# Light_Control.net
KiCad netlist of a schematic drawn in Altium Designer
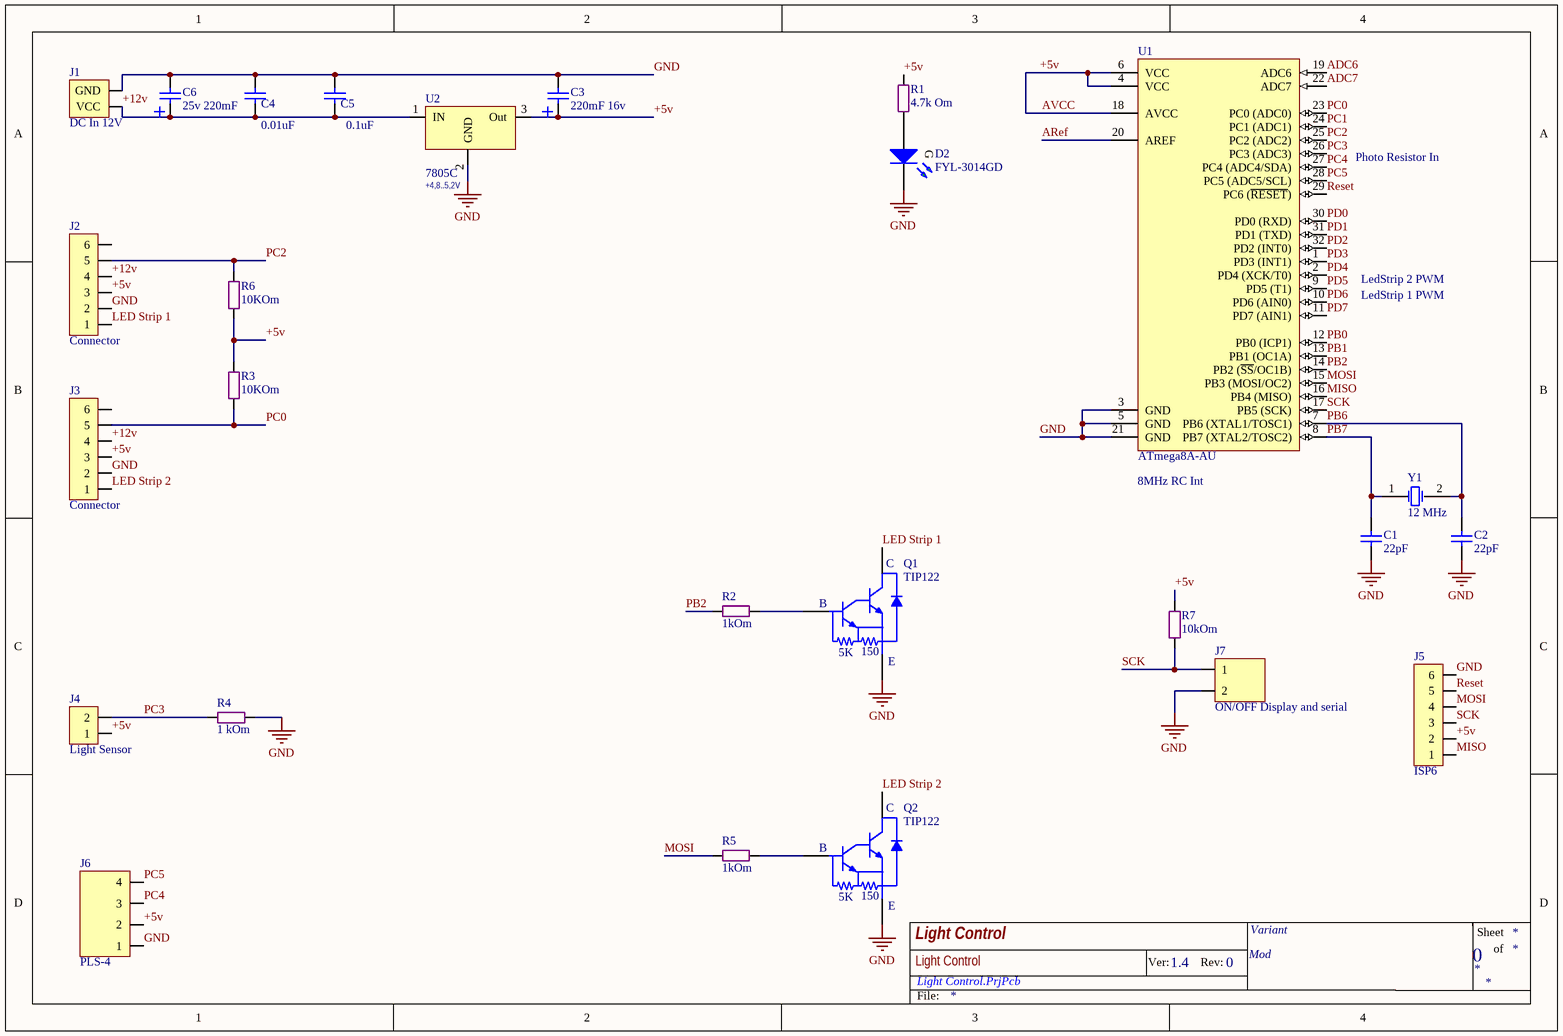
[diagram p0: Light Control.SchDoc]

(export (version "E")
  (design (tool "Eeschema 10.0.6"))
  (components
    (comp (ref "C1")
      (value "22pF")
      (footprint "Capacitor:SMD 0805 (2012)")
      (description "Capacitor")
      (libsource (lib "Capacitor") (part "Cap SMD 0402-1812"))
    )
    (comp (ref "C2")
      (value "22pF")
      (footprint "Capacitor:SMD 0805 (2012)")
      (description "Capacitor")
      (libsource (lib "Capacitor") (part "Cap SMD 0402-1812"))
    )
    (comp (ref "C3")
      (value "220mF 16v")
      (footprint "Capacitor:Cap E p2mm D6.5xH11")
      (description "Capacitor")
      (libsource (lib "Capacitor") (part "Cap E 220mF x 16V"))
    )
    (comp (ref "C4")
      (value "0.01uF")
      (footprint "Capacitor:SMD 0805 (2012)")
      (description "Capacitor")
      (libsource (lib "Capacitor") (part "Cap SMD 0402-1812"))
    )
    (comp (ref "C5")
      (value "0.1uF")
      (footprint "Capacitor:SMD 0805 (2012)")
      (description "Capacitor")
      (libsource (lib "Capacitor") (part "Cap SMD 0402-1812"))
    )
    (comp (ref "C6")
      (value "25v 220mF")
      (footprint "Capacitor:Cap E p2mm D6.5xH11")
      (description "Capacitor")
      (libsource (lib "Capacitor") (part "Cap E 220mF x 16V"))
    )
    (comp (ref "D2")
      (value "FYL-3014GD")
      (footprint "LED:LED Round 3mm Green")
      (description "2.1v 10mA, 15-30mCd")
      (libsource (lib "LED") (part "Led Round 3mm Green"))
    )
    (comp (ref "J1")
      (value "DC In 12V")
      (footprint "Connector:DC Connector")
      (description "DC Connector")
      (libsource (lib "Connector") (part "DC Connector (PJ-002B)"))
    )
    (comp (ref "J2")
      (value "Connector")
      (footprint "Connector:Molex Micro-Fit 3.0 - 6 pin D R")
      (description "Horisontal, Dbl line, Male - 3mm")
      (libsource (lib "Connector") (part "Micro-Fit 6R (2x3)"))
    )
    (comp (ref "J3")
      (value "Connector")
      (footprint "Connector:Molex Micro-Fit 3.0 - 6 pin D R")
      (description "Horisontal, Dbl line, Male - 3mm")
      (libsource (lib "Connector") (part "Micro-Fit 6R (2x3)"))
    )
    (comp (ref "J4")
      (value "Light Sensor")
      (footprint "Connector:Molex Micro-Fit 3.0 - 2 pin D R")
      (description "Horisontal, Dbl line, Male - 3mm")
      (fields (field (name "PART NUMBER") "430450200"))
      (libsource (lib "Connector") (part "Micro-Fit 2R (1x2)"))
    )
    (comp (ref "J5")
      (value "ISP6")
      (footprint "Connector:LINE 2.54 x 6D (2 x 3)")
      (description "Vert, Dbl line, Male")
      (libsource (lib "Connector") (part "PLD-6 (2 x 3)"))
    )
    (comp (ref "J6")
      (value "PLS-4")
      (footprint "Connector:Line 2.54 X 4")
      (description "Vert, Sgl line, Male")
      (libsource (lib "Connector") (part "PLS-4"))
    )
    (comp (ref "J7")
      (value "ON/OFF Display and serial")
      (footprint "Connector:Line 2.54 x 2")
      (description "Vert, Sgl line, Male")
      (libsource (lib "Connector") (part "PLS-2"))
    )
    (comp (ref "Q1")
      (value "TIP122")
      (footprint "GeneralCases:TO220-2")
      (description "NPN Darlington 5A, 65W, 100V, h>1000")
      (libsource (lib "Transistor") (part "TIP122"))
    )
    (comp (ref "Q2")
      (value "TIP122")
      (footprint "GeneralCases:TO220-2")
      (description "NPN Darlington 5A, 65W, 100V, h>1000")
      (libsource (lib "Transistor") (part "TIP122"))
    )
    (comp (ref "R1")
      (value "4.7k Om")
      (footprint "PassiveComponents:SMD 0805 (2012)")
      (libsource (lib "PassiveComponents") (part "Res All Types"))
    )
    (comp (ref "R2")
      (value "1kOm")
      (footprint "PassiveComponents:Res 0.25w - 7p")
      (libsource (lib "PassiveComponents") (part "Res All Types"))
    )
    (comp (ref "R3")
      (value "10KOm")
      (footprint "PassiveComponents:SMD 0805 (2012)")
      (libsource (lib "PassiveComponents") (part "Res All Types"))
    )
    (comp (ref "R4")
      (value "1 kOm")
      (footprint "PassiveComponents:SMD 0805 (2012)")
      (libsource (lib "PassiveComponents") (part "Res All Types"))
    )
    (comp (ref "R5")
      (value "1kOm")
      (footprint "PassiveComponents:SMD 1206 (3216)")
      (libsource (lib "PassiveComponents") (part "Res All Types"))
    )
    (comp (ref "R6")
      (value "10KOm")
      (footprint "PassiveComponents:SMD 0805 (2012)")
      (libsource (lib "PassiveComponents") (part "Res All Types"))
    )
    (comp (ref "R7")
      (value "10kOm")
      (footprint "PassiveComponents:SMD 0805 (2012)")
      (libsource (lib "PassiveComponents") (part "Res All Types"))
    )
    (comp (ref "U1")
      (value "ATmega8A-AU")
      (footprint "32A_M")
      (fields (field (name "PUBLISHER") "Altium Limited"))
      (libsource (lib "Atmel Microcontroller 8-Bit megaAVR") (part "ATmega8A-AU"))
    )
    (comp (ref "U2")
      (value "7805C")
      (footprint "GeneralCases:D-PAK")
      (description "Voltage Regulator")
      (fields (field (name "MANUFACTURER") "Интеграл") (field (name "V OUT") "+4,8..5,2V"))
      (libsource (lib "PowerAdjusment") (part "7805C"))
    )
    (comp (ref "Y1")
      (value "12 MHz")
      (footprint "PassiveComponents:XTAL - 2")
      (description "Crystal Oscillator")
      (fields (field (name "PUBLISHER") "Altium Limited"))
      (libsource (lib "PassiveComponents") (part "XTAL"))
    )
  )
  (nets
    (net (code "1") (name "/+5v") (class "Default")
      (node (ref "C3") (pin "1") (pinfunction "1_1") (pintype "passive"))
      (node (ref "J2") (pin "3") (pinfunction "3_3") (pintype "passive"))
      (node (ref "J3") (pin "3") (pinfunction "3_3") (pintype "passive"))
      (node (ref "J4") (pin "1") (pinfunction "1_1") (pintype "passive"))
      (node (ref "J5") (pin "2") (pinfunction "2_2") (pintype "passive"))
      (node (ref "J6") (pin "2") (pinfunction "2_2") (pintype "passive"))
      (node (ref "R1") (pin "1") (pinfunction "1_1") (pintype "passive"))
      (node (ref "R3") (pin "2") (pinfunction "2_2") (pintype "passive"))
      (node (ref "R6") (pin "1") (pinfunction "1_1") (pintype "passive"))
      (node (ref "R7") (pin "2") (pinfunction "2_2") (pintype "passive"))
      (node (ref "U1") (pin "18") (pinfunction "AVCC_18") (pintype "power_in"))
      (node (ref "U1") (pin "4") (pinfunction "VCC_4") (pintype "power_in"))
      (node (ref "U1") (pin "6") (pinfunction "VCC_6") (pintype "power_in"))
      (node (ref "U2") (pin "3") (pinfunction "Out_3") (pintype "power_in"))
    )
    (net (code "2") (name "/+12v") (class "Default")
      (node (ref "C4") (pin "2") (pinfunction "2_2") (pintype "passive"))
      (node (ref "C5") (pin "2") (pinfunction "2_2") (pintype "passive"))
      (node (ref "C6") (pin "1") (pinfunction "1_1") (pintype "passive"))
      (node (ref "J1") (pin "VCC") (pinfunction "VCC_VCC") (pintype "passive"))
      (node (ref "J2") (pin "4") (pinfunction "4_4") (pintype "passive"))
      (node (ref "J3") (pin "4") (pinfunction "4_4") (pintype "passive"))
      (node (ref "U2") (pin "1") (pinfunction "IN_1") (pintype "power_in"))
    )
    (net (code "3") (name "/ADC6") (class "Default")
      (node (ref "U1") (pin "19") (pinfunction "ADC6_19") (pintype "input"))
    )
    (net (code "4") (name "/ADC7") (class "Default")
      (node (ref "U1") (pin "22") (pinfunction "ADC7_22") (pintype "input"))
    )
    (net (code "5") (name "/ARef") (class "Default")
      (node (ref "U1") (pin "20") (pinfunction "AREF_20") (pintype "power_in"))
    )
    (net (code "6") (name "/LED Strip 1") (class "Default")
      (node (ref "J2") (pin "1") (pinfunction "1_1") (pintype "passive"))
      (node (ref "Q1") (pin "2") (pinfunction "C_2") (pintype "passive"))
    )
    (net (code "7") (name "/LED Strip 2") (class "Default")
      (node (ref "J3") (pin "1") (pinfunction "1_1") (pintype "passive"))
      (node (ref "Q2") (pin "2") (pinfunction "C_2") (pintype "passive"))
    )
    (net (code "8") (name "/MISO") (class "Default")
      (node (ref "J5") (pin "1") (pinfunction "1_1") (pintype "passive"))
      (node (ref "U1") (pin "16") (pinfunction "PB4_(MISO)_16") (pintype "bidirectional"))
    )
    (net (code "9") (name "/MOSI") (class "Default")
      (node (ref "J5") (pin "4") (pinfunction "4_4") (pintype "passive"))
      (node (ref "R5") (pin "1") (pinfunction "1_1") (pintype "passive"))
      (node (ref "U1") (pin "15") (pinfunction "PB3_(MOSI/OC2)_15") (pintype "bidirectional"))
    )
    (net (code "10") (name "/PB0") (class "Default")
      (node (ref "U1") (pin "12") (pinfunction "PB0_(ICP1)_12") (pintype "bidirectional"))
    )
    (net (code "11") (name "/PB1") (class "Default")
      (node (ref "U1") (pin "13") (pinfunction "PB1_(OC1A)_13") (pintype "bidirectional"))
    )
    (net (code "12") (name "/PB2") (class "Default")
      (node (ref "R2") (pin "1") (pinfunction "1_1") (pintype "passive"))
      (node (ref "U1") (pin "14") (pinfunction "PB2_(~{SS}/OC1B)_14") (pintype "bidirectional"))
    )
    (net (code "13") (name "/PB6") (class "Default")
      (node (ref "C2") (pin "2") (pinfunction "2_2") (pintype "passive"))
      (node (ref "U1") (pin "7") (pinfunction "PB6_(XTAL1/TOSC1)_7") (pintype "bidirectional"))
      (node (ref "Y1") (pin "2") (pinfunction "OSC2_2") (pintype "passive"))
    )
    (net (code "14") (name "/PB7") (class "Default")
      (node (ref "C1") (pin "2") (pinfunction "2_2") (pintype "passive"))
      (node (ref "U1") (pin "8") (pinfunction "PB7_(XTAL2/TOSC2)_8") (pintype "bidirectional"))
      (node (ref "Y1") (pin "1") (pinfunction "OSC1_1") (pintype "passive"))
    )
    (net (code "15") (name "/PC0") (class "Default")
      (node (ref "J3") (pin "5") (pinfunction "5_5") (pintype "passive"))
      (node (ref "R3") (pin "1") (pinfunction "1_1") (pintype "passive"))
      (node (ref "U1") (pin "23") (pinfunction "PC0_(ADC0)_23") (pintype "bidirectional"))
    )
    (net (code "16") (name "/PC1") (class "Default")
      (node (ref "U1") (pin "24") (pinfunction "PC1_(ADC1)_24") (pintype "bidirectional"))
    )
    (net (code "17") (name "/PC2") (class "Default")
      (node (ref "J2") (pin "5") (pinfunction "5_5") (pintype "passive"))
      (node (ref "R6") (pin "2") (pinfunction "2_2") (pintype "passive"))
      (node (ref "U1") (pin "25") (pinfunction "PC2_(ADC2)_25") (pintype "bidirectional"))
    )
    (net (code "18") (name "/PC3") (class "Default")
      (node (ref "J4") (pin "2") (pinfunction "2_2") (pintype "passive"))
      (node (ref "R4") (pin "1") (pinfunction "1_1") (pintype "passive"))
      (node (ref "U1") (pin "26") (pinfunction "PC3_(ADC3)_26") (pintype "bidirectional"))
    )
    (net (code "19") (name "/PC4") (class "Default")
      (node (ref "J6") (pin "3") (pinfunction "3_3") (pintype "passive"))
      (node (ref "U1") (pin "27") (pinfunction "PC4_(ADC4/SDA)_27") (pintype "bidirectional"))
    )
    (net (code "20") (name "/PC5") (class "Default")
      (node (ref "J6") (pin "4") (pinfunction "4_4") (pintype "passive"))
      (node (ref "U1") (pin "28") (pinfunction "PC5_(ADC5/SCL)_28") (pintype "bidirectional"))
    )
    (net (code "21") (name "/PD0") (class "Default")
      (node (ref "U1") (pin "30") (pinfunction "PD0_(RXD)_30") (pintype "bidirectional"))
    )
    (net (code "22") (name "/PD1") (class "Default")
      (node (ref "U1") (pin "31") (pinfunction "PD1_(TXD)_31") (pintype "bidirectional"))
    )
    (net (code "23") (name "/PD2") (class "Default")
      (node (ref "U1") (pin "32") (pinfunction "PD2_(INT0)_32") (pintype "bidirectional"))
    )
    (net (code "24") (name "/PD3") (class "Default")
      (node (ref "U1") (pin "1") (pinfunction "PD3_(INT1)_1") (pintype "bidirectional"))
    )
    (net (code "25") (name "/PD4") (class "Default")
      (node (ref "U1") (pin "2") (pinfunction "PD4_(XCK/T0)_2") (pintype "bidirectional"))
    )
    (net (code "26") (name "/PD5") (class "Default")
      (node (ref "U1") (pin "9") (pinfunction "PD5_(T1)_9") (pintype "bidirectional"))
    )
    (net (code "27") (name "/PD6") (class "Default")
      (node (ref "U1") (pin "10") (pinfunction "PD6_(AIN0)_10") (pintype "bidirectional"))
    )
    (net (code "28") (name "/PD7") (class "Default")
      (node (ref "U1") (pin "11") (pinfunction "PD7_(AIN1)_11") (pintype "bidirectional"))
    )
    (net (code "29") (name "/Reset") (class "Default")
      (node (ref "J5") (pin "5") (pinfunction "5_5") (pintype "passive"))
      (node (ref "U1") (pin "29") (pinfunction "PC6_(~{RESET})_29") (pintype "bidirectional"))
    )
    (net (code "30") (name "/SCK") (class "Default")
      (node (ref "J5") (pin "3") (pinfunction "3_3") (pintype "passive"))
      (node (ref "J7") (pin "1") (pinfunction "1_1") (pintype "passive"))
      (node (ref "R7") (pin "1") (pinfunction "1_1") (pintype "passive"))
      (node (ref "U1") (pin "17") (pinfunction "PB5_(SCK)_17") (pintype "bidirectional"))
    )
    (net (code "31") (name "GND") (class "Default")
      (node (ref "C1") (pin "1") (pinfunction "1_1") (pintype "passive"))
      (node (ref "C2") (pin "1") (pinfunction "1_1") (pintype "passive"))
      (node (ref "C3") (pin "2") (pinfunction "2_2") (pintype "passive"))
      (node (ref "C4") (pin "1") (pinfunction "1_1") (pintype "passive"))
      (node (ref "C5") (pin "1") (pinfunction "1_1") (pintype "passive"))
      (node (ref "C6") (pin "2") (pinfunction "2_2") (pintype "passive"))
      (node (ref "D2") (pin "K") (pinfunction "K_K") (pintype "passive"))
      (node (ref "J1") (pin "GND") (pinfunction "GND_GND") (pintype "passive"))
      (node (ref "J2") (pin "2") (pinfunction "2_2") (pintype "passive"))
      (node (ref "J3") (pin "2") (pinfunction "2_2") (pintype "passive"))
      (node (ref "J5") (pin "6") (pinfunction "6_6") (pintype "passive"))
      (node (ref "J6") (pin "1") (pinfunction "1_1") (pintype "passive"))
      (node (ref "J7") (pin "2") (pinfunction "2_2") (pintype "passive"))
      (node (ref "Q1") (pin "3") (pinfunction "E_3") (pintype "passive"))
      (node (ref "Q2") (pin "3") (pinfunction "E_3") (pintype "passive"))
      (node (ref "R4") (pin "2") (pinfunction "2_2") (pintype "passive"))
      (node (ref "U1") (pin "21") (pinfunction "GND_21") (pintype "power_in"))
      (node (ref "U1") (pin "3") (pinfunction "GND_3") (pintype "power_in"))
      (node (ref "U1") (pin "5") (pinfunction "GND_5") (pintype "power_in"))
      (node (ref "U2") (pin "2") (pinfunction "GND_2") (pintype "passive"))
    )
    (net (code "32") (name "Net-(D2-PadA)") (class "Default")
      (node (ref "D2") (pin "A") (pinfunction "A_A") (pintype "passive"))
      (node (ref "R1") (pin "2") (pinfunction "2_2") (pintype "passive"))
    )
    (net (code "33") (name "Net-(Q1-B)") (class "Default")
      (node (ref "Q1") (pin "1") (pinfunction "B_1") (pintype "passive"))
      (node (ref "R2") (pin "2") (pinfunction "2_2") (pintype "passive"))
    )
    (net (code "34") (name "Net-(Q2-B)") (class "Default")
      (node (ref "Q2") (pin "1") (pinfunction "B_1") (pintype "passive"))
      (node (ref "R5") (pin "2") (pinfunction "2_2") (pintype "passive"))
    )
    (net (code "35") (name "unconnected-(J2-Pad6)") (class "Default")
      (node (ref "J2") (pin "6") (pinfunction "6_6") (pintype "passive"))
    )
    (net (code "36") (name "unconnected-(J3-Pad6)") (class "Default")
      (node (ref "J3") (pin "6") (pinfunction "6_6") (pintype "passive"))
    )
  )
)
